# groundhog-thr-REVA.net
KiCad netlist of a schematic drawn in EAGLE
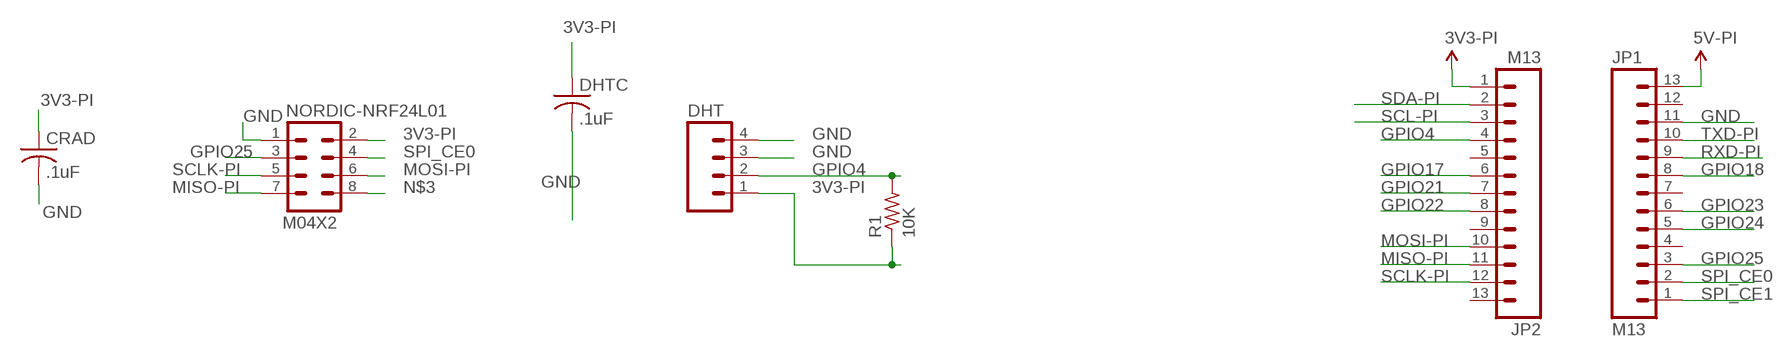
[diagram p0: schematic, sheet 1]

(export (version "E")
  (design (tool "Eeschema 10.0.6"))
  (components
    (comp (ref "CRAD")
      (value ".1uF")
      (footprint "eagle-import:C0805")
      (libsource (lib "eagle-import") (part "C-USC0805"))
    )
    (comp (ref "DHT")
      (value "M04PTH")
      (footprint "eagle-import:1X04")
      (libsource (lib "eagle-import") (part "M04PTH"))
    )
    (comp (ref "DHTC")
      (value ".1uF")
      (footprint "eagle-import:C0805")
      (libsource (lib "eagle-import") (part "C-USC0805"))
    )
    (comp (ref "JP1")
      (value "M13")
      (footprint "eagle-import:1X13")
      (libsource (lib "eagle-import") (part "M13"))
    )
    (comp (ref "JP2")
      (value "M13")
      (footprint "eagle-import:1X13")
      (libsource (lib "eagle-import") (part "M13"))
    )
    (comp (ref "NORDIC-NRF24L01")
      (value "M04X2")
      (footprint "eagle-import:2X4")
      (libsource (lib "eagle-import") (part "M04X2"))
    )
    (comp (ref "R1")
      (value "10K")
      (footprint "eagle-import:R0805")
      (libsource (lib "eagle-import") (part "R-US_R0805"))
    )
  )
  (nets
    (net (code "1") (name "/GND") (class "Default")
      (node (ref "CRAD") (pin "2") (pinfunction "2_2") (pintype "passive"))
      (node (ref "DHT") (pin "3") (pinfunction "3_3") (pintype "passive"))
      (node (ref "DHT") (pin "4") (pinfunction "4_4") (pintype "passive"))
      (node (ref "DHTC") (pin "2") (pinfunction "2_2") (pintype "passive"))
      (node (ref "JP1") (pin "11") (pinfunction "11_11") (pintype "passive"))
      (node (ref "NORDIC-NRF24L01") (pin "1") (pinfunction "1_1") (pintype "passive"))
    )
    (net (code "2") (name "/GPIO4") (class "Default")
      (node (ref "DHT") (pin "2") (pinfunction "2_2") (pintype "passive"))
      (node (ref "JP2") (pin "4") (pinfunction "4_4") (pintype "passive"))
      (node (ref "R1") (pin "2") (pinfunction "2_2") (pintype "passive"))
    )
    (net (code "3") (name "/GPIO17") (class "Default")
      (node (ref "JP2") (pin "6") (pinfunction "6_6") (pintype "passive"))
    )
    (net (code "4") (name "/GPIO18") (class "Default")
      (node (ref "JP1") (pin "8") (pinfunction "8_8") (pintype "passive"))
    )
    (net (code "5") (name "/GPIO21") (class "Default")
      (node (ref "JP2") (pin "7") (pinfunction "7_7") (pintype "passive"))
    )
    (net (code "6") (name "/GPIO22") (class "Default")
      (node (ref "JP2") (pin "8") (pinfunction "8_8") (pintype "passive"))
    )
    (net (code "7") (name "/GPIO23") (class "Default")
      (node (ref "JP1") (pin "6") (pinfunction "6_6") (pintype "passive"))
    )
    (net (code "8") (name "/GPIO24") (class "Default")
      (node (ref "JP1") (pin "5") (pinfunction "5_5") (pintype "passive"))
    )
    (net (code "9") (name "/GPIO25") (class "Default")
      (node (ref "JP1") (pin "3") (pinfunction "3_3") (pintype "passive"))
      (node (ref "NORDIC-NRF24L01") (pin "3") (pinfunction "3_3") (pintype "passive"))
    )
    (net (code "10") (name "/MISO-PI") (class "Default")
      (node (ref "JP2") (pin "11") (pinfunction "11_11") (pintype "passive"))
      (node (ref "NORDIC-NRF24L01") (pin "7") (pinfunction "7_7") (pintype "passive"))
    )
    (net (code "11") (name "/MOSI-PI") (class "Default")
      (node (ref "JP2") (pin "10") (pinfunction "10_10") (pintype "passive"))
      (node (ref "NORDIC-NRF24L01") (pin "6") (pinfunction "6_6") (pintype "passive"))
    )
    (net (code "12") (name "/N$3") (class "Default")
      (node (ref "NORDIC-NRF24L01") (pin "8") (pinfunction "8_8") (pintype "passive"))
    )
    (net (code "13") (name "/RXD-PI") (class "Default")
      (node (ref "JP1") (pin "9") (pinfunction "9_9") (pintype "passive"))
    )
    (net (code "14") (name "/SCL-PI") (class "Default")
      (node (ref "JP2") (pin "3") (pinfunction "3_3") (pintype "passive"))
    )
    (net (code "15") (name "/SCLK-PI") (class "Default")
      (node (ref "JP2") (pin "12") (pinfunction "12_12") (pintype "passive"))
      (node (ref "NORDIC-NRF24L01") (pin "5") (pinfunction "5_5") (pintype "passive"))
    )
    (net (code "16") (name "/SDA-PI") (class "Default")
      (node (ref "JP2") (pin "2") (pinfunction "2_2") (pintype "passive"))
    )
    (net (code "17") (name "/SPI_CE0") (class "Default")
      (node (ref "JP1") (pin "2") (pinfunction "2_2") (pintype "passive"))
      (node (ref "NORDIC-NRF24L01") (pin "4") (pinfunction "4_4") (pintype "passive"))
    )
    (net (code "18") (name "/SPI_CE1") (class "Default")
      (node (ref "JP1") (pin "1") (pinfunction "1_1") (pintype "passive"))
    )
    (net (code "19") (name "/TXD-PI") (class "Default")
      (node (ref "JP1") (pin "10") (pinfunction "10_10") (pintype "passive"))
    )
    (net (code "20") (name "3V3-PI") (class "Default")
      (node (ref "CRAD") (pin "1") (pinfunction "1_1") (pintype "passive"))
      (node (ref "DHT") (pin "1") (pinfunction "1_1") (pintype "passive"))
      (node (ref "DHTC") (pin "1") (pinfunction "1_1") (pintype "passive"))
      (node (ref "JP2") (pin "1") (pinfunction "1_1") (pintype "passive"))
      (node (ref "NORDIC-NRF24L01") (pin "2") (pinfunction "2_2") (pintype "passive"))
      (node (ref "R1") (pin "1") (pinfunction "1_1") (pintype "passive"))
    )
    (net (code "21") (name "5V-PI") (class "Default")
      (node (ref "JP1") (pin "13") (pinfunction "13_13") (pintype "passive"))
    )
    (net (code "22") (name "unconnected-(JP1-Pad4)") (class "Default")
      (node (ref "JP1") (pin "4") (pinfunction "4_4") (pintype "passive"))
    )
    (net (code "23") (name "unconnected-(JP1-Pad7)") (class "Default")
      (node (ref "JP1") (pin "7") (pinfunction "7_7") (pintype "passive"))
    )
    (net (code "24") (name "unconnected-(JP1-Pad12)") (class "Default")
      (node (ref "JP1") (pin "12") (pinfunction "12_12") (pintype "passive"))
    )
    (net (code "25") (name "unconnected-(JP2-Pad5)") (class "Default")
      (node (ref "JP2") (pin "5") (pinfunction "5_5") (pintype "passive"))
    )
    (net (code "26") (name "unconnected-(JP2-Pad9)") (class "Default")
      (node (ref "JP2") (pin "9") (pinfunction "9_9") (pintype "passive"))
    )
    (net (code "27") (name "unconnected-(JP2-Pad13)") (class "Default")
      (node (ref "JP2") (pin "13") (pinfunction "13_13") (pintype "passive"))
    )
  )
)
